# 10_MISC.net
KiCad netlist of a schematic drawn in Altium Designer
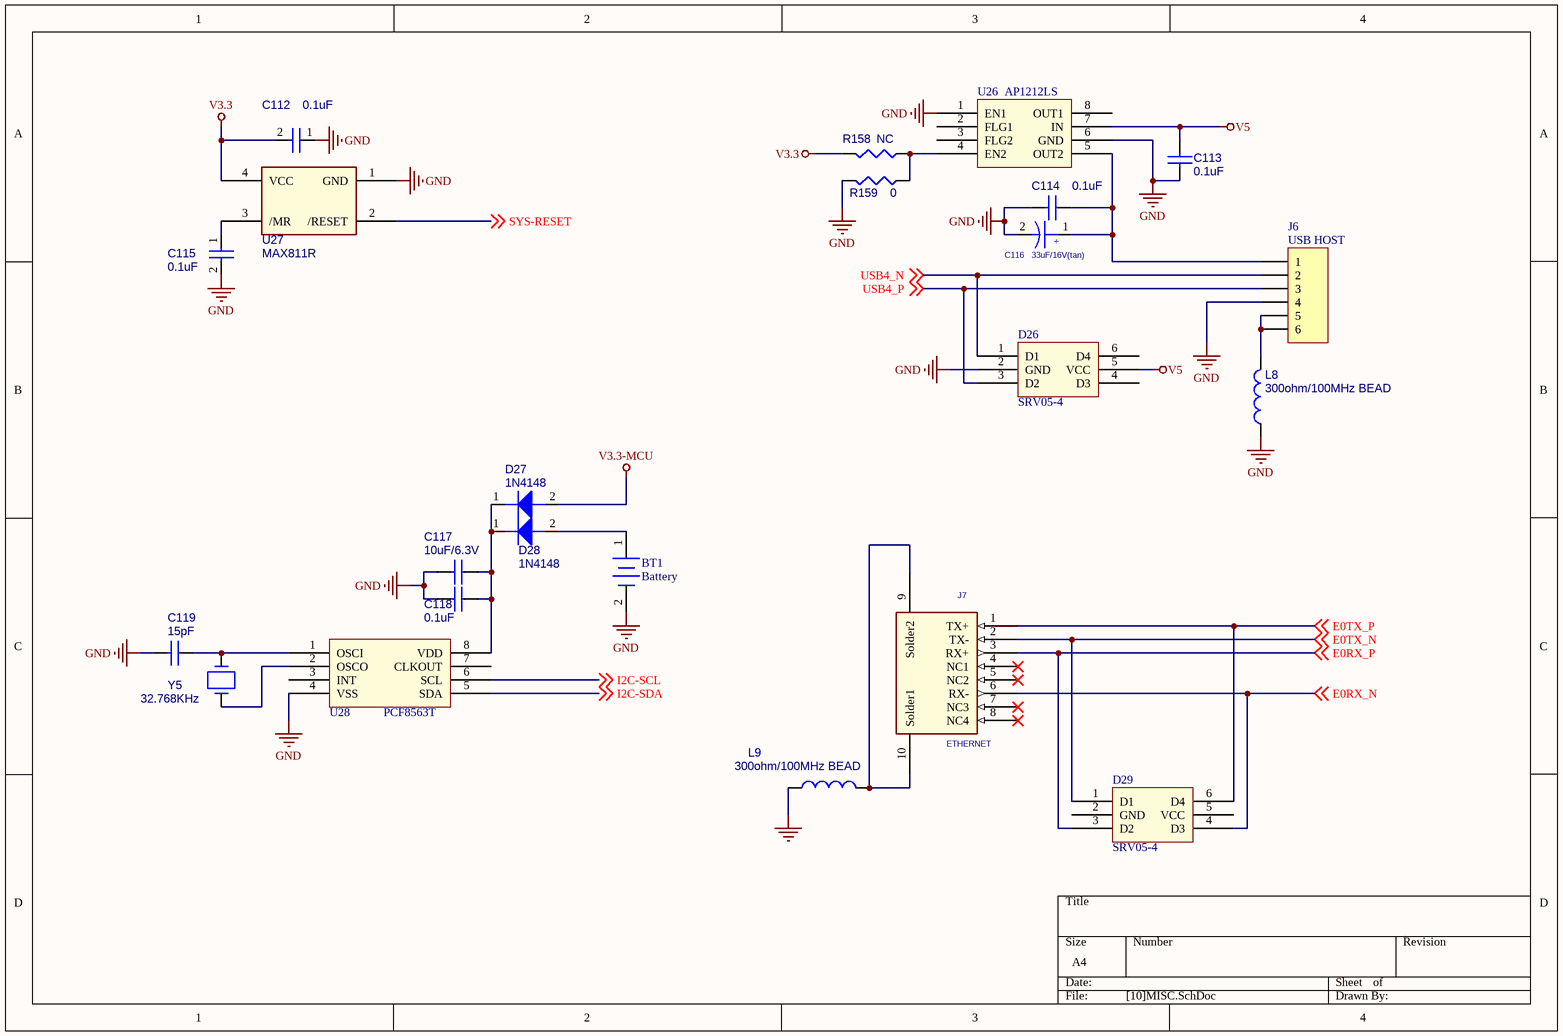
[diagram p0: [10]MISC.SchDoc]

(export (version "E")
  (design (tool "Eeschema 10.0.6"))
  (components
    (comp (ref "BT1")
      (value "Battery")
      (footprint "CR1220")
      (description "Multicell Battery")
      (libsource (lib "Miscellaneous Devices") (part "Battery"))
    )
    (comp (ref "C112") (value "0.1uF") (libsource (lib "*") (part "CAP NP_Dup2")))
    (comp (ref "C113") (value "0.1uF") (libsource (lib "*") (part "CAP_Dup1")))
    (comp (ref "C114") (value "0.1uF") (libsource (lib "*") (part "CAP_Dup1")))
    (comp (ref "C115") (value "0.1uF") (libsource (lib "*") (part "CAP NP_Dup2")))
    (comp (ref "C116") (value "33uF/16V(tan)") (footprint "3528") (libsource (lib "*") (part "CAP WP")))
    (comp (ref "C117") (value "10uF/6.3V") (footprint "0805") (libsource (lib "*") (part "CAP_Dup1")))
    (comp (ref "C118") (value "0.1uF") (libsource (lib "*") (part "CAP_Dup1")))
    (comp (ref "C119") (value "15pF") (libsource (lib "*") (part "CAP_Dup1")))
    (comp (ref "D26") (value "SRV05-4") (footprint "SOT23-6") (libsource (lib "Schlib") (part "SRV05-4")))
    (comp (ref "D27")
      (value "1N4148")
      (footprint "MINI-MELF")
      (libsource (lib "*") (part "1N4148WS-7-F_SOD323-2"))
    )
    (comp (ref "D28")
      (value "1N4148")
      (footprint "MINI-MELF")
      (libsource (lib "*") (part "1N4148WS-7-F_SOD323-2"))
    )
    (comp (ref "D29") (value "SRV05-4") (footprint "SOT23-6") (libsource (lib "Schlib") (part "SRV05-4")))
    (comp (ref "J6")
      (value "USB HOST")
      (footprint "USB-HOST")
      (description "Header, 6-Pin")
      (libsource (lib "Miscellaneous Connectors") (part "Header 6"))
    )
    (comp (ref "J7") (value "ETHERNET") (libsource (lib "*") (part "NET")))
    (comp (ref "L8") (value "300ohm/100MHz BEAD") (libsource (lib "*") (part "INDUCTOR_4")))
    (comp (ref "L9") (value "300ohm/100MHz BEAD") (libsource (lib "*") (part "INDUCTOR_4")))
    (comp (ref "R158")
      (value "NC")
      (fields (field (name "PART NUMBER") "SD02810028L"))
      (libsource (lib "*") (part "R"))
    )
    (comp (ref "R159")
      (value "0")
      (fields (field (name "PART NUMBER") "SD02810028L"))
      (libsource (lib "*") (part "R"))
    )
    (comp (ref "U26") (value "AP1212LS") (footprint "SO8") (libsource (lib "Schlib") (part "AP1212")))
    (comp (ref "U27") (value "MAX811R") (libsource (lib "*") (part "MAX811")))
    (comp (ref "U28") (value "PCF8563T") (footprint "SO8") (libsource (lib "Schlib") (part "PCF8563T")))
    (comp (ref "Y5") (value "32.768KHz") (libsource (lib "*") (part "CRYSTAL")))
  )
  (nets
    (net (code "1") (name "E0RX_N") (class "Default")
      (node (ref "D29") (pin "4") (pinfunction "D3_4") (pintype "passive"))
      (node (ref "J7") (pin "6") (pinfunction "RX-_6") (pintype "output"))
    )
    (net (code "2") (name "E0RX_P") (class "Default")
      (node (ref "D29") (pin "3") (pinfunction "D2_3") (pintype "passive"))
      (node (ref "J7") (pin "3") (pinfunction "RX+_3") (pintype "output"))
    )
    (net (code "3") (name "E0TX_N") (class "Default")
      (node (ref "D29") (pin "1") (pinfunction "D1_1") (pintype "passive"))
      (node (ref "J7") (pin "2") (pinfunction "TX-_2") (pintype "input"))
    )
    (net (code "4") (name "E0TX_P") (class "Default")
      (node (ref "D29") (pin "6") (pinfunction "D4_6") (pintype "passive"))
      (node (ref "J7") (pin "1") (pinfunction "TX+_1") (pintype "input"))
    )
    (net (code "5") (name "GND") (class "Default")
      (node (ref "BT1") (pin "2") (pinfunction "-_2") (pintype "passive"))
      (node (ref "C112") (pin "1") (pinfunction "1_1") (pintype "passive"))
      (node (ref "C113") (pin "2") (pinfunction "2_2") (pintype "passive"))
      (node (ref "C114") (pin "2") (pinfunction "2_2") (pintype "passive"))
      (node (ref "C115") (pin "2") (pinfunction "2_2") (pintype "passive"))
      (node (ref "C116") (pin "2") (pinfunction "2_2") (pintype "passive"))
      (node (ref "C117") (pin "2") (pinfunction "2_2") (pintype "passive"))
      (node (ref "C118") (pin "2") (pinfunction "2_2") (pintype "passive"))
      (node (ref "C119") (pin "2") (pinfunction "2_2") (pintype "passive"))
      (node (ref "D26") (pin "2") (pinfunction "GND_2") (pintype "passive"))
      (node (ref "J6") (pin "4") (pinfunction "4_4") (pintype "passive"))
      (node (ref "L8") (pin "2") (pinfunction "2_2") (pintype "passive"))
      (node (ref "L9") (pin "2") (pinfunction "2_2") (pintype "passive"))
      (node (ref "R159") (pin "2") (pinfunction "2_2") (pintype "passive"))
      (node (ref "U26") (pin "1") (pinfunction "EN1_1") (pintype "passive"))
      (node (ref "U26") (pin "6") (pinfunction "GND_6") (pintype "passive"))
      (node (ref "U27") (pin "1") (pinfunction "GND_1") (pintype "passive"))
      (node (ref "U28") (pin "4") (pinfunction "VSS_4") (pintype "passive"))
    )
    (net (code "6") (name "I2C-SCL") (class "Default")
      (node (ref "U28") (pin "6") (pinfunction "SCL_6") (pintype "passive"))
    )
    (net (code "7") (name "I2C-SDA") (class "Default")
      (node (ref "U28") (pin "5") (pinfunction "SDA_5") (pintype "passive"))
    )
    (net (code "8") (name "Net-(BT1-+)") (class "Default")
      (node (ref "BT1") (pin "1") (pinfunction "+_1") (pintype "passive"))
      (node (ref "D28") (pin "2") (pinfunction "2_2") (pintype "passive"))
    )
    (net (code "9") (name "Net-(J6-Pad5)") (class "Default")
      (node (ref "J6") (pin "5") (pinfunction "5_5") (pintype "passive"))
      (node (ref "J6") (pin "6") (pinfunction "6_6") (pintype "passive"))
      (node (ref "L8") (pin "1") (pinfunction "1_1") (pintype "passive"))
    )
    (net (code "10") (name "Net-(J7-Solder1)") (class "Default")
      (node (ref "J7") (pin "10") (pinfunction "Solder1_10") (pintype "passive"))
      (node (ref "J7") (pin "9") (pinfunction "Solder2_9") (pintype "passive"))
      (node (ref "L9") (pin "1") (pinfunction "1_1") (pintype "passive"))
    )
    (net (code "11") (name "Net-(U26-EN2)") (class "Default")
      (node (ref "R158") (pin "1") (pinfunction "1_1") (pintype "passive"))
      (node (ref "R159") (pin "1") (pinfunction "1_1") (pintype "passive"))
      (node (ref "U26") (pin "4") (pinfunction "EN2_4") (pintype "passive"))
    )
    (net (code "12") (name "Net-(U26-OUT2)") (class "Default")
      (node (ref "C114") (pin "1") (pinfunction "1_1") (pintype "passive"))
      (node (ref "C116") (pin "1") (pinfunction "1_1") (pintype "passive"))
      (node (ref "J6") (pin "1") (pinfunction "1_1") (pintype "passive"))
      (node (ref "U26") (pin "5") (pinfunction "OUT2_5") (pintype "passive"))
    )
    (net (code "13") (name "Net-(U27-{slash}MR)") (class "Default")
      (node (ref "C115") (pin "1") (pinfunction "1_1") (pintype "passive"))
      (node (ref "U27") (pin "3") (pinfunction "/MR_3") (pintype "passive"))
    )
    (net (code "14") (name "Net-(U28-OSCI)") (class "Default")
      (node (ref "C119") (pin "1") (pinfunction "1_1") (pintype "passive"))
      (node (ref "U28") (pin "1") (pinfunction "OSCI_1") (pintype "passive"))
      (node (ref "Y5") (pin "2") (pinfunction "2_2") (pintype "passive"))
    )
    (net (code "15") (name "Net-(U28-OSCO)") (class "Default")
      (node (ref "U28") (pin "2") (pinfunction "OSCO_2") (pintype "passive"))
      (node (ref "Y5") (pin "1") (pinfunction "1_1") (pintype "passive"))
    )
    (net (code "16") (name "Net-(U28-VDD)") (class "Default")
      (node (ref "C117") (pin "1") (pinfunction "1_1") (pintype "passive"))
      (node (ref "C118") (pin "1") (pinfunction "1_1") (pintype "passive"))
      (node (ref "D27") (pin "1") (pinfunction "1_1") (pintype "passive"))
      (node (ref "D28") (pin "1") (pinfunction "1_1") (pintype "passive"))
      (node (ref "U28") (pin "8") (pinfunction "VDD_8") (pintype "passive"))
    )
    (net (code "17") (name "SYS-RESET") (class "Default")
      (node (ref "U27") (pin "2") (pinfunction "/RESET_2") (pintype "passive"))
    )
    (net (code "18") (name "USB4_N") (class "Default")
      (node (ref "D26") (pin "1") (pinfunction "D1_1") (pintype "passive"))
      (node (ref "J6") (pin "2") (pinfunction "2_2") (pintype "passive"))
    )
    (net (code "19") (name "USB4_P") (class "Default")
      (node (ref "D26") (pin "3") (pinfunction "D2_3") (pintype "passive"))
      (node (ref "J6") (pin "3") (pinfunction "3_3") (pintype "passive"))
    )
    (net (code "20") (name "V3.3") (class "Default")
      (node (ref "C112") (pin "2") (pinfunction "2_2") (pintype "passive"))
      (node (ref "R158") (pin "2") (pinfunction "2_2") (pintype "passive"))
      (node (ref "U27") (pin "4") (pinfunction "VCC_4") (pintype "passive"))
    )
    (net (code "21") (name "V3.3-MCU") (class "Default")
      (node (ref "D27") (pin "2") (pinfunction "2_2") (pintype "passive"))
    )
    (net (code "22") (name "V5") (class "Default")
      (node (ref "C113") (pin "1") (pinfunction "1_1") (pintype "passive"))
      (node (ref "D26") (pin "5") (pinfunction "VCC_5") (pintype "passive"))
      (node (ref "U26") (pin "7") (pinfunction "IN_7") (pintype "passive"))
    )
    (net (code "23") (name "unconnected-(D26-D3-Pad4)") (class "Default")
      (node (ref "D26") (pin "4") (pinfunction "D3_4") (pintype "passive"))
    )
    (net (code "24") (name "unconnected-(D26-D4-Pad6)") (class "Default")
      (node (ref "D26") (pin "6") (pinfunction "D4_6") (pintype "passive"))
    )
    (net (code "25") (name "unconnected-(D29-GND-Pad2)") (class "Default")
      (node (ref "D29") (pin "2") (pinfunction "GND_2") (pintype "passive"))
    )
    (net (code "26") (name "unconnected-(D29-VCC-Pad5)") (class "Default")
      (node (ref "D29") (pin "5") (pinfunction "VCC_5") (pintype "passive"))
    )
    (net (code "27") (name "unconnected-(J7-NC1-Pad4)") (class "Default")
      (node (ref "J7") (pin "4") (pinfunction "NC1_4") (pintype "input+no_connect"))
    )
    (net (code "28") (name "unconnected-(J7-NC2-Pad5)") (class "Default")
      (node (ref "J7") (pin "5") (pinfunction "NC2_5") (pintype "input+no_connect"))
    )
    (net (code "29") (name "unconnected-(J7-NC3-Pad7)") (class "Default")
      (node (ref "J7") (pin "7") (pinfunction "NC3_7") (pintype "input+no_connect"))
    )
    (net (code "30") (name "unconnected-(J7-NC4-Pad8)") (class "Default")
      (node (ref "J7") (pin "8") (pinfunction "NC4_8") (pintype "input+no_connect"))
    )
    (net (code "31") (name "unconnected-(U26-FLG1-Pad2)") (class "Default")
      (node (ref "U26") (pin "2") (pinfunction "FLG1_2") (pintype "passive"))
    )
    (net (code "32") (name "unconnected-(U26-FLG2-Pad3)") (class "Default")
      (node (ref "U26") (pin "3") (pinfunction "FLG2_3") (pintype "passive"))
    )
    (net (code "33") (name "unconnected-(U26-OUT1-Pad8)") (class "Default")
      (node (ref "U26") (pin "8") (pinfunction "OUT1_8") (pintype "passive"))
    )
    (net (code "34") (name "unconnected-(U28-CLKOUT-Pad7)") (class "Default")
      (node (ref "U28") (pin "7") (pinfunction "CLKOUT_7") (pintype "passive"))
    )
    (net (code "35") (name "unconnected-(U28-INT-Pad3)") (class "Default")
      (node (ref "U28") (pin "3") (pinfunction "INT_3") (pintype "passive"))
    )
  )
)
